# LaunchyIgnition.net
KiCad netlist of a schematic drawn in Altium Designer
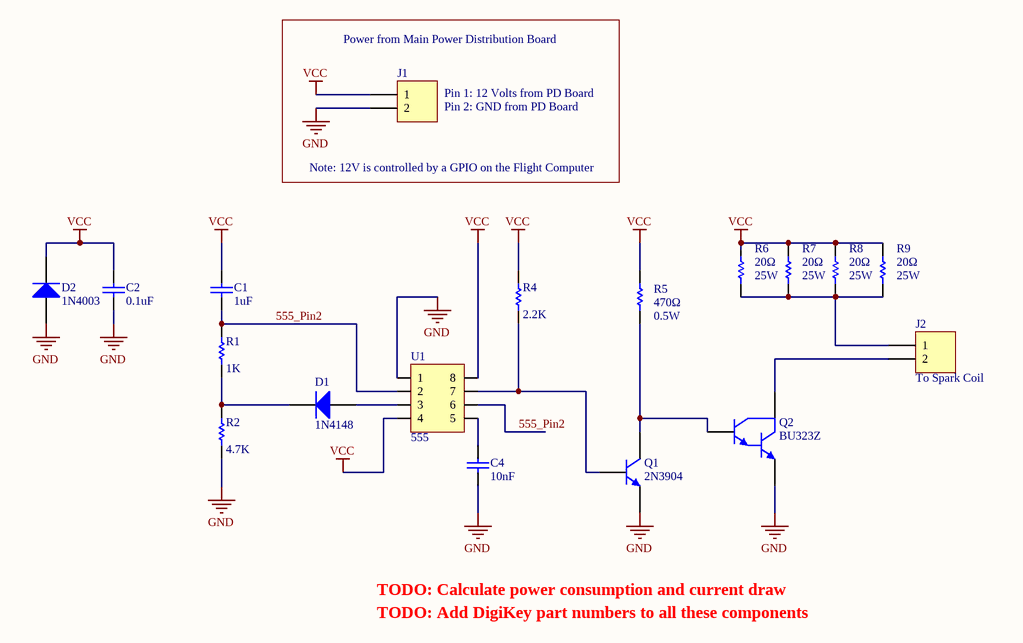
[diagram p0: LaunchyIgnition.SchDoc]

(export (version "E")
  (design (tool "Eeschema 10.0.6"))
  (components
    (comp (ref "C1")
      (value "1uF")
      (footprint "Cap-0805")
      (description "Capacitor")
      (fields (field (name "PUBLISHER") "Altium Limited"))
      (libsource (lib "Miscellaneous Devices") (part "Cap"))
    )
    (comp (ref "C2")
      (value "0.1uF")
      (footprint "Cap-0805")
      (description "Capacitor")
      (fields (field (name "PUBLISHER") "Altium Limited"))
      (libsource (lib "Miscellaneous Devices") (part "Cap"))
    )
    (comp (ref "C4")
      (value "10nF")
      (footprint "Cap-0805")
      (description "Capacitor")
      (fields (field (name "PUBLISHER") "Altium Limited"))
      (libsource (lib "Miscellaneous Devices") (part "Cap"))
    )
    (comp (ref "D1")
      (value "1N4148")
      (footprint "SOD-123")
      (libsource (lib "Miscellaneous Devices") (part "Diode 1N4148"))
    )
    (comp (ref "D2")
      (value "1N4003")
      (footprint "DO-41")
      (libsource (lib "Miscellaneous Devices") (part "Diode 1N4148"))
    )
    (comp (ref "J1")
      (value "Header 2")
      (footprint "WPJ-2")
      (description "Header, 2-Pin")
      (fields (field (name "PUBLISHER") "Altium Limited"))
      (libsource (lib "Miscellaneous Connectors") (part "Header 2"))
    )
    (comp (ref "J2")
      (value "To Spark Coil")
      (footprint "WPJ-2")
      (description "Header, 2-Pin")
      (libsource (lib "Miscellaneous Connectors") (part "Header 2"))
    )
    (comp (ref "Q1")
      (value "2N3904")
      (footprint "TO-226-AA")
      (description "NPN Bipolar Transistor")
      (fields (field (name "PUBLISHER") "Altium Limited"))
      (libsource (lib "Miscellaneous Devices") (part "NPN"))
    )
    (comp (ref "Q2")
      (value "BU323Z")
      (footprint "TO-92")
      (description "NPN Darlington Bipolar Transistor")
      (fields (field (name "PUBLISHER") "Altium Limited"))
      (libsource (lib "Miscellaneous Devices") (part "NPN1"))
    )
    (comp (ref "R1")
      (value "1K")
      (footprint "Res-0805")
      (description "Resistor")
      (fields (field (name "Comment") "Res1") (field (name "PUBLISHER") "Altium Limited"))
      (libsource (lib "Miscellaneous Devices") (part "Res1"))
    )
    (comp (ref "R2")
      (value "4.7K")
      (footprint "Res-0805")
      (description "Resistor")
      (fields (field (name "Comment") "Res1") (field (name "PUBLISHER") "Altium Limited"))
      (libsource (lib "Miscellaneous Devices") (part "Res1"))
    )
    (comp (ref "R4")
      (value "2.2K")
      (footprint "Res-0805")
      (description "Resistor")
      (fields (field (name "Comment") "Res1") (field (name "PUBLISHER") "Altium Limited"))
      (libsource (lib "Miscellaneous Devices") (part "Res1"))
    )
    (comp (ref "R5")
      (value "470Ω")
      (footprint "Res-0805")
      (description "Resistor")
      (fields
        (field (name "MAX POWER") "0.5W")
        (field (name "Comment") "Res1")
        (field (name "PUBLISHER") "Altium Limited")
      )
      (libsource (lib "Miscellaneous Devices") (part "Res1"))
    )
    (comp (ref "R6")
      (value "20Ω")
      (footprint "Res-0805")
      (description "Resistor")
      (fields
        (field (name "MAX POWER") "25W")
        (field (name "Comment") "Res1")
        (field (name "PUBLISHER") "Altium Limited")
      )
      (libsource (lib "Miscellaneous Devices") (part "Res1"))
    )
    (comp (ref "R7")
      (value "20Ω")
      (footprint "Res-0805")
      (description "Resistor")
      (fields
        (field (name "MAX POWER") "25W")
        (field (name "Comment") "Res1")
        (field (name "PUBLISHER") "Altium Limited")
      )
      (libsource (lib "Miscellaneous Devices") (part "Res1"))
    )
    (comp (ref "R8")
      (value "20Ω")
      (footprint "Res-0805")
      (description "Resistor")
      (fields
        (field (name "MAX POWER") "25W")
        (field (name "Comment") "Res1")
        (field (name "PUBLISHER") "Altium Limited")
      )
      (libsource (lib "Miscellaneous Devices") (part "Res1"))
    )
    (comp (ref "R9")
      (value "20Ω")
      (footprint "Res-0805")
      (description "Resistor")
      (fields
        (field (name "MAX POWER") "25W")
        (field (name "Comment") "Res1")
        (field (name "PUBLISHER") "Altium Limited")
      )
      (libsource (lib "Miscellaneous Devices") (part "Res1"))
    )
    (comp (ref "U1")
      (value "555")
      (footprint "8-SOIC")
      (description "IC OSC SGL TIMER 2.1MHZ 8-SOIC")
      (fields (field (name "MANUFACTURER PART NUMBER") "TLC555CDR"))
      (libsource (lib "LaunchyIgnitionParts") (part "555"))
    )
  )
  (nets
    (net (code "1") (name "/555_Pin2") (class "Default")
      (node (ref "C1") (pin "1") (pinfunction "1_1") (pintype "passive"))
      (node (ref "R1") (pin "2") (pinfunction "2_2") (pintype "passive"))
      (node (ref "U1") (pin "2") (pinfunction "2_2") (pintype "passive"))
      (node (ref "U1") (pin "6") (pinfunction "6_6") (pintype "passive"))
    )
    (net (code "2") (name "GND") (class "Default")
      (node (ref "C2") (pin "1") (pinfunction "1_1") (pintype "passive"))
      (node (ref "C4") (pin "1") (pinfunction "1_1") (pintype "passive"))
      (node (ref "D2") (pin "1") (pinfunction "A_1") (pintype "passive"))
      (node (ref "J1") (pin "2") (pinfunction "2_2") (pintype "passive"))
      (node (ref "Q1") (pin "3") (pinfunction "E_3") (pintype "passive"))
      (node (ref "Q2") (pin "3") (pinfunction "E_3") (pintype "passive"))
      (node (ref "R2") (pin "1") (pinfunction "1_1") (pintype "passive"))
      (node (ref "U1") (pin "1") (pinfunction "1_1") (pintype "passive"))
    )
    (net (code "3") (name "Net-(C4-Pad2)") (class "Default")
      (node (ref "C4") (pin "2") (pinfunction "2_2") (pintype "passive"))
      (node (ref "U1") (pin "5") (pinfunction "5_5") (pintype "passive"))
    )
    (net (code "4") (name "Net-(D1-A)") (class "Default")
      (node (ref "D1") (pin "1") (pinfunction "A_1") (pintype "passive"))
      (node (ref "U1") (pin "3") (pinfunction "3_3") (pintype "passive"))
    )
    (net (code "5") (name "Net-(D1-K)") (class "Default")
      (node (ref "D1") (pin "2") (pinfunction "K_2") (pintype "passive"))
      (node (ref "R1") (pin "1") (pinfunction "1_1") (pintype "passive"))
      (node (ref "R2") (pin "2") (pinfunction "2_2") (pintype "passive"))
    )
    (net (code "6") (name "Net-(J2-Pad1)") (class "Default")
      (node (ref "J2") (pin "1") (pinfunction "1_1") (pintype "passive"))
      (node (ref "R6") (pin "1") (pinfunction "1_1") (pintype "passive"))
      (node (ref "R7") (pin "1") (pinfunction "1_1") (pintype "passive"))
      (node (ref "R8") (pin "1") (pinfunction "1_1") (pintype "passive"))
      (node (ref "R9") (pin "1") (pinfunction "1_1") (pintype "passive"))
    )
    (net (code "7") (name "Net-(Q1-B)") (class "Default")
      (node (ref "Q1") (pin "2") (pinfunction "B_2") (pintype "passive"))
      (node (ref "R4") (pin "1") (pinfunction "1_1") (pintype "passive"))
      (node (ref "U1") (pin "7") (pinfunction "7_7") (pintype "passive"))
    )
    (net (code "8") (name "Net-(Q1-C)") (class "Default")
      (node (ref "Q1") (pin "1") (pinfunction "C_1") (pintype "passive"))
      (node (ref "Q2") (pin "2") (pinfunction "B_2") (pintype "passive"))
      (node (ref "R5") (pin "1") (pinfunction "1_1") (pintype "passive"))
    )
    (net (code "9") (name "Net-(Q2-C)") (class "Default")
      (node (ref "J2") (pin "2") (pinfunction "2_2") (pintype "passive"))
      (node (ref "Q2") (pin "1") (pinfunction "C_1") (pintype "passive"))
    )
    (net (code "10") (name "VCC") (class "Default")
      (node (ref "C1") (pin "2") (pinfunction "2_2") (pintype "passive"))
      (node (ref "C2") (pin "2") (pinfunction "2_2") (pintype "passive"))
      (node (ref "D2") (pin "2") (pinfunction "K_2") (pintype "passive"))
      (node (ref "J1") (pin "1") (pinfunction "1_1") (pintype "passive"))
      (node (ref "R4") (pin "2") (pinfunction "2_2") (pintype "passive"))
      (node (ref "R5") (pin "2") (pinfunction "2_2") (pintype "passive"))
      (node (ref "R6") (pin "2") (pinfunction "2_2") (pintype "passive"))
      (node (ref "R7") (pin "2") (pinfunction "2_2") (pintype "passive"))
      (node (ref "R8") (pin "2") (pinfunction "2_2") (pintype "passive"))
      (node (ref "R9") (pin "2") (pinfunction "2_2") (pintype "passive"))
      (node (ref "U1") (pin "4") (pinfunction "4_4") (pintype "passive"))
      (node (ref "U1") (pin "8") (pinfunction "8_8") (pintype "passive"))
    )
  )
)
